# Jacdac_Pressure_Sensor-RevA-Maker.net
KiCad netlist of a schematic drawn in EAGLE
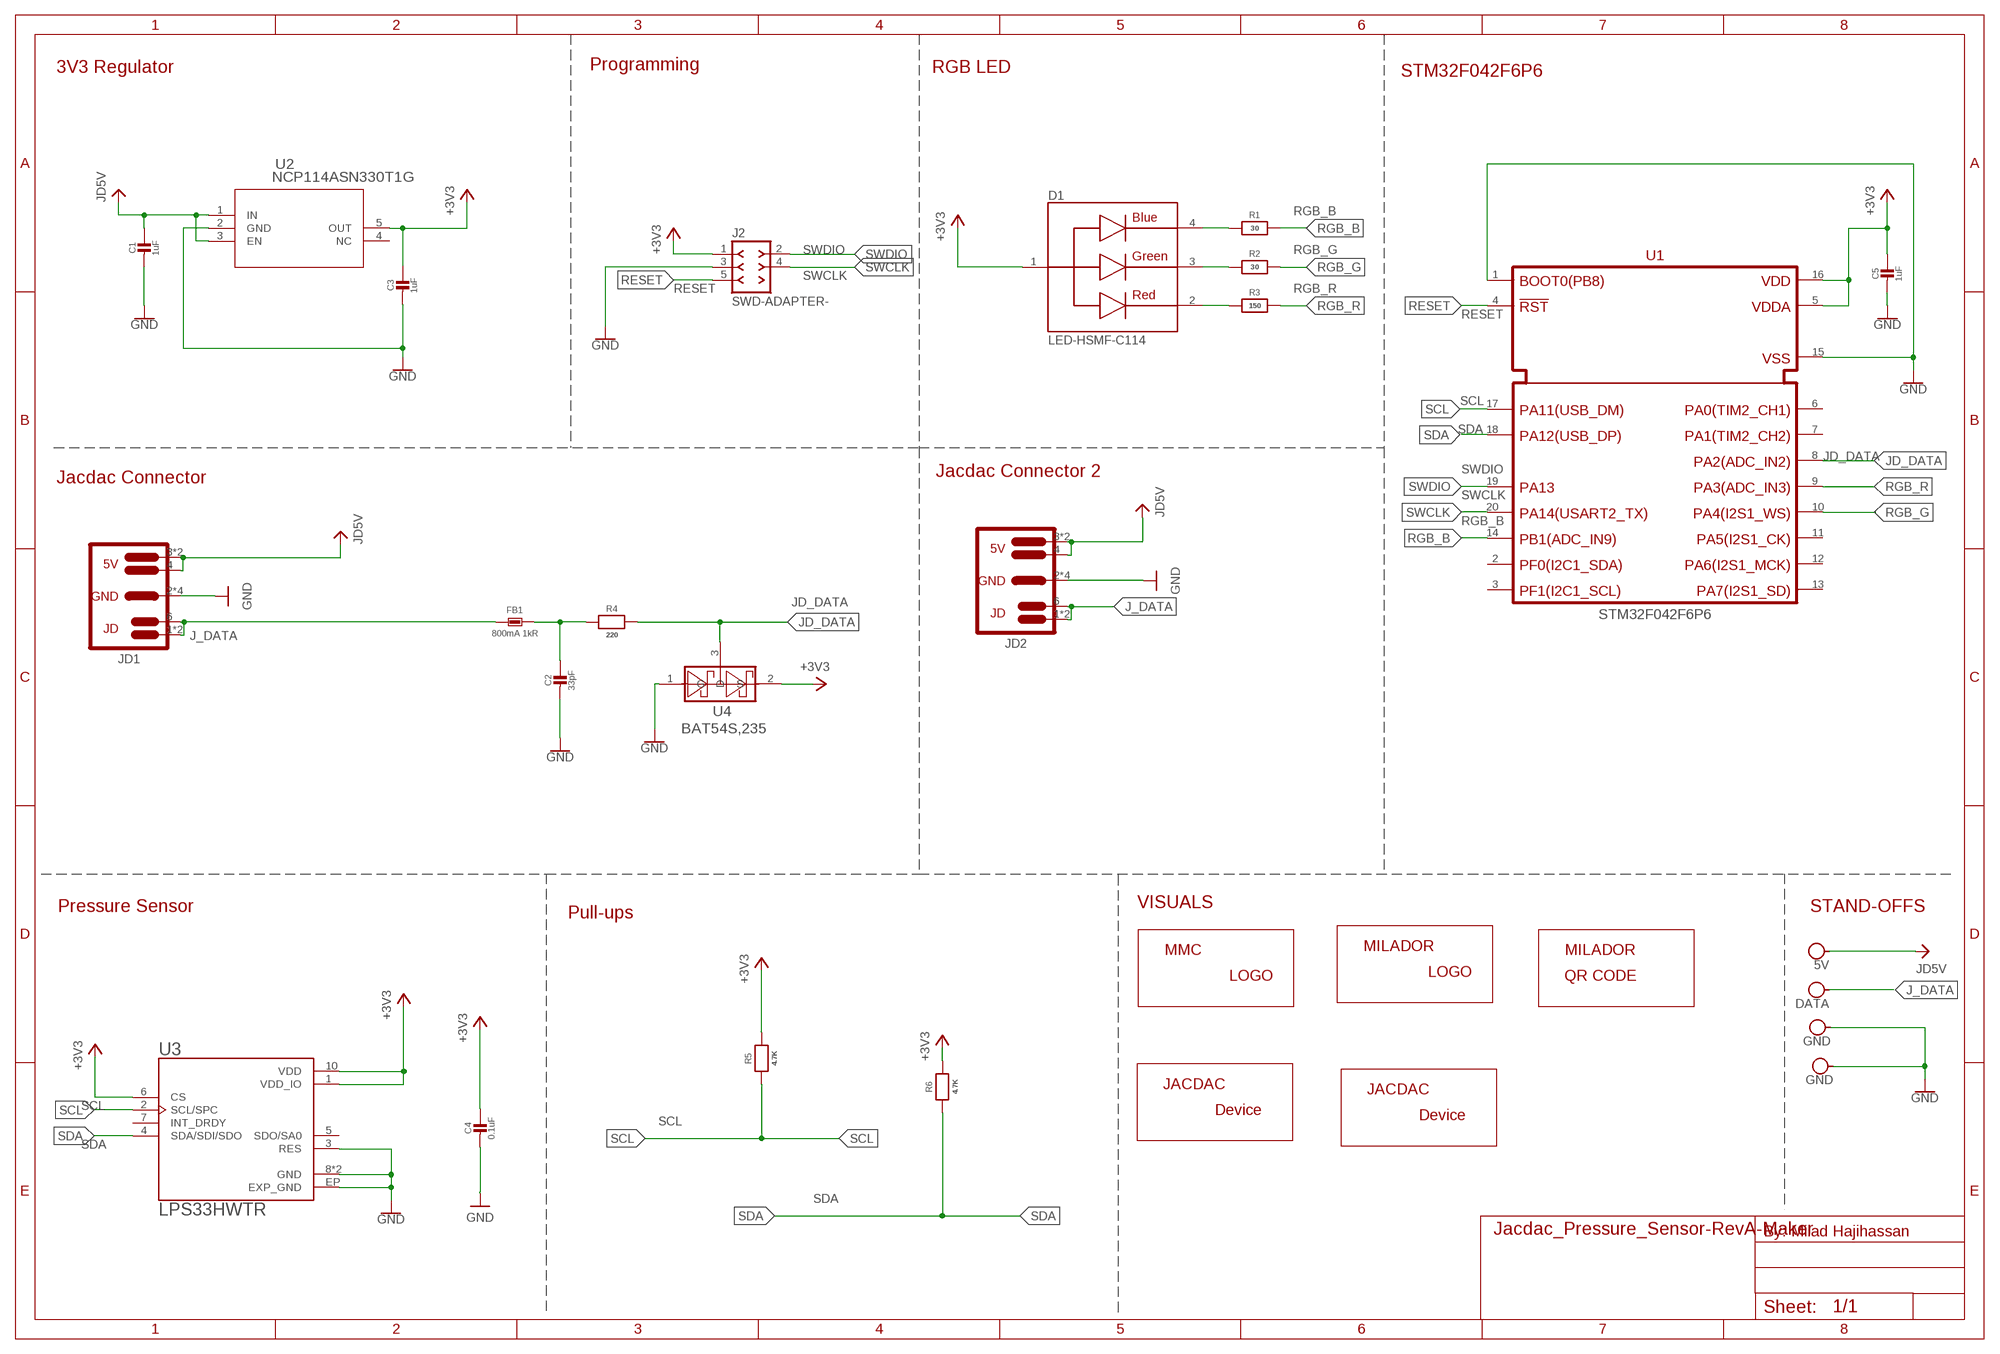
[diagram p0: schematic, sheet 1]

(export (version "E")
  (design (tool "Eeschema 10.0.6"))
  (components
    (comp (ref "C1")
      (value "1uF")
      (footprint "eagle-import:0603-NO")
      (libsource (lib "eagle-import") (part "CAP_CERAMIC-0603-NO"))
    )
    (comp (ref "C2")
      (value "33pF")
      (footprint "eagle-import:0603")
      (libsource (lib "eagle-import") (part "CAP_CERAMIC-0603"))
    )
    (comp (ref "C3")
      (value "1uF")
      (footprint "eagle-import:0603-NO")
      (libsource (lib "eagle-import") (part "CAP_CERAMIC-0603-NO"))
    )
    (comp (ref "C4")
      (value "0.1uF")
      (footprint "eagle-import:0603-NO")
      (libsource (lib "eagle-import") (part "CAP_CERAMIC-0603-NO"))
    )
    (comp (ref "C5")
      (value "1uF")
      (footprint "eagle-import:0603")
      (libsource (lib "eagle-import") (part "CAP_CERAMIC-0603"))
    )
    (comp (ref "D1")
      (value "LED-HSMF-C114")
      (footprint "eagle-import:DIOSC160X150X35-4N")
      (fields (field (name "MF") "Broadcom Limited") (field (name "MP") "HSMF-C114"))
      (libsource (lib "eagle-import") (part "LED-HSMF-C114"))
    )
    (comp (ref "FB1")
      (value "800mA 1kR")
      (footprint "eagle-import:0603-NO")
      (libsource (lib "eagle-import") (part "FERRITE-BEAD-0603-NO"))
    )
    (comp (ref "J2")
      (value "SWD-ADAPTER-")
      (footprint "eagle-import:SWD-ADAPTER")
      (libsource (lib "eagle-import") (part "SWD-ADAPTER-"))
    )
    (comp (ref "J3")
      (value "5V")
      (footprint "eagle-import:M3-HOLE-PWR-OUTL")
      (libsource (lib "eagle-import") (part "JACDAC-M3-PWR-OUTL"))
    )
    (comp (ref "J4")
      (value "DATA")
      (footprint "eagle-import:M3-HOLE-DATA-NOTCH")
      (libsource (lib "eagle-import") (part "JACDAC-M3-DATA-NOTCH"))
    )
    (comp (ref "J5")
      (value "GND")
      (footprint "eagle-import:M3-HOLE-GND")
      (libsource (lib "eagle-import") (part "JACDAC-M3-GND"))
    )
    (comp (ref "J6")
      (value "GND")
      (footprint "eagle-import:M3-HOLE-GND")
      (libsource (lib "eagle-import") (part "JACDAC-M3-GND"))
    )
    (comp (ref "JD1")
      (value "JACDAC-EDGE-OUTIE")
      (footprint "eagle-import:JD-EDGE-OUTIE")
      (libsource (lib "eagle-import") (part "JACDAC-EDGE-OUTIE"))
    )
    (comp (ref "JD2")
      (value "JACDAC-EDGE-OUTIE")
      (footprint "eagle-import:JD-EDGE-OUTIE")
      (libsource (lib "eagle-import") (part "JACDAC-EDGE-OUTIE"))
    )
    (comp (ref "LABEL_JACDAC_PS")
      (value "MILADOR-JACDAC-DEVICE-PS")
      (footprint "eagle-import:JACDAC-PRESSURE-SENSOR")
      (libsource (lib "eagle-import") (part "MILADOR-JACDAC-DEVICE-PS"))
    )
    (comp (ref "LABEL_LPS33HW")
      (value "MILADOR-JACDAC-DEVICE-LPS33HW")
      (footprint "eagle-import:JACDAC-LPS33HW")
      (libsource (lib "eagle-import") (part "MILADOR-JACDAC-DEVICE-LPS33HW"))
    )
    (comp (ref "LABEL_MILADOR")
      (value "MILADOR-LOGO-")
      (footprint "eagle-import:MILADOR_LOGO1")
      (libsource (lib "eagle-import") (part "MILADOR-LOGO-"))
    )
    (comp (ref "LABEL_QR_CODE")
      (value "MILADOR-QR-CODE-JACDAC-GITHUB-PS")
      (footprint "eagle-import:MILADOR_QR_JACDAC_PS")
      (libsource (lib "eagle-import") (part "MILADOR-QR-CODE-JACDAC-GITHUB-PS"))
    )
    (comp (ref "MMC_LOGO")
      (value "MMC_LOGO-XSM")
      (footprint "eagle-import:MMC_X-SMALL_LOGO")
      (libsource (lib "eagle-import") (part "MMC_LOGO-XSM"))
    )
    (comp (ref "R1")
      (value "30")
      (footprint "eagle-import:0603")
      (libsource (lib "eagle-import") (part "RESISTOR-0603"))
    )
    (comp (ref "R2")
      (value "30")
      (footprint "eagle-import:0603")
      (libsource (lib "eagle-import") (part "RESISTOR-0603"))
    )
    (comp (ref "R3")
      (value "150")
      (footprint "eagle-import:0603")
      (libsource (lib "eagle-import") (part "RESISTOR-0603"))
    )
    (comp (ref "R4")
      (value "220")
      (footprint "eagle-import:0603")
      (libsource (lib "eagle-import") (part "RESISTOR-0603"))
    )
    (comp (ref "R5")
      (value "4.7K")
      (footprint "eagle-import:0603")
      (libsource (lib "eagle-import") (part "RESISTOR-0603"))
    )
    (comp (ref "R6")
      (value "4.7K")
      (footprint "eagle-import:0603")
      (libsource (lib "eagle-import") (part "RESISTOR-0603"))
    )
    (comp (ref "U1")
      (value "STM32F042F6P6")
      (footprint "eagle-import:TSSOP20")
      (libsource (lib "eagle-import") (part "STM32F042F6P6"))
    )
    (comp (ref "U2")
      (value "NCP114ASN330T1G")
      (footprint "eagle-import:TSOP-5_ONS")
      (fields (field (name "COPYRIGHT") "Copyright (C) 2021 Ultra Librarian. All rights reserved."))
      (libsource (lib "eagle-import") (part "NCP114ASN330T1G"))
    )
    (comp (ref "U3")
      (value "LPS33HWTR")
      (footprint "eagle-import:PQFN60P330X330X290-11N")
      (fields (field (name "DIGI-KEY_PART_NUMBER") "497-17590-1-ND") (field (name "MF") "STMicroelectronics"))
      (libsource (lib "eagle-import") (part "LPS33HWTR"))
    )
    (comp (ref "U4")
      (value "BAT54S,235")
      (footprint "eagle-import:SOT23-3")
      (fields (field (name "MF") "Diodes") (field (name "MP") "BSS138-7-F"))
      (libsource (lib "eagle-import") (part "BAT54S,235"))
    )
  )
  (nets
    (net (code "1") (name "+3V3") (class "Default")
      (node (ref "C3") (pin "1") (pinfunction "1_1") (pintype "passive"))
      (node (ref "C4") (pin "1") (pinfunction "1_1") (pintype "passive"))
      (node (ref "C5") (pin "1") (pinfunction "1_1") (pintype "passive"))
      (node (ref "D1") (pin "1") (pinfunction "1_1") (pintype "passive"))
      (node (ref "J2") (pin "1") (pinfunction "VCC_1_1") (pintype "passive"))
      (node (ref "R5") (pin "2") (pinfunction "2_2") (pintype "passive"))
      (node (ref "R6") (pin "2") (pinfunction "2_2") (pintype "passive"))
      (node (ref "U1") (pin "16") (pinfunction "VDD_16") (pintype "input"))
      (node (ref "U1") (pin "5") (pinfunction "VDDA_5") (pintype "input"))
      (node (ref "U2") (pin "5") (pinfunction "OUT_5") (pintype "power_in"))
      (node (ref "U3") (pin "1") (pinfunction "VDD_IO_1") (pintype "power_in"))
      (node (ref "U3") (pin "10") (pinfunction "VDD_10") (pintype "power_in"))
      (node (ref "U3") (pin "6") (pinfunction "CS_6") (pintype "bidirectional"))
      (node (ref "U4") (pin "2") (pinfunction "S_2") (pintype "passive"))
    )
    (net (code "2") (name "GND") (class "Default")
      (node (ref "C1") (pin "2") (pinfunction "2_2") (pintype "passive"))
      (node (ref "C2") (pin "2") (pinfunction "2_2") (pintype "passive"))
      (node (ref "C3") (pin "2") (pinfunction "2_2") (pintype "passive"))
      (node (ref "C4") (pin "2") (pinfunction "2_2") (pintype "passive"))
      (node (ref "C5") (pin "2") (pinfunction "2_2") (pintype "passive"))
      (node (ref "J2") (pin "3") (pinfunction "GND_3_3") (pintype "passive"))
      (node (ref "J5") (pin "H") (pinfunction "P$1_H") (pintype "bidirectional"))
      (node (ref "J6") (pin "H") (pinfunction "P$1_H") (pintype "bidirectional"))
      (node (ref "JD1") (pin "2") (pinfunction "1_2") (pintype "power_in"))
      (node (ref "JD1") (pin "5") (pinfunction "1_5") (pintype "power_in"))
      (node (ref "JD1") (pin "P$2") (pinfunction "1_P$2") (pintype "power_in"))
      (node (ref "JD1") (pin "P$4") (pinfunction "1_P$4") (pintype "power_in"))
      (node (ref "JD2") (pin "2") (pinfunction "1_2") (pintype "power_in"))
      (node (ref "JD2") (pin "5") (pinfunction "1_5") (pintype "power_in"))
      (node (ref "JD2") (pin "P$2") (pinfunction "1_P$2") (pintype "power_in"))
      (node (ref "JD2") (pin "P$4") (pinfunction "1_P$4") (pintype "power_in"))
      (node (ref "U1") (pin "1") (pinfunction "BOOT0_1") (pintype "input"))
      (node (ref "U1") (pin "15") (pinfunction "VSS_15") (pintype "input"))
      (node (ref "U2") (pin "2") (pinfunction "GND_2") (pintype "passive"))
      (node (ref "U3") (pin "3") (pinfunction "RES_3") (pintype "passive"))
      (node (ref "U3") (pin "8") (pinfunction "GND_8") (pintype "power_in"))
      (node (ref "U3") (pin "9") (pinfunction "GND_9") (pintype "power_in"))
      (node (ref "U3") (pin "EP") (pinfunction "EXP_GND_EP") (pintype "power_in"))
      (node (ref "U4") (pin "1") (pinfunction "G_1") (pintype "passive"))
    )
    (net (code "3") (name "JD5V") (class "Default")
      (node (ref "C1") (pin "1") (pinfunction "1_1") (pintype "passive"))
      (node (ref "J3") (pin "H") (pinfunction "P$1_H") (pintype "bidirectional"))
      (node (ref "JD1") (pin "3") (pinfunction "3_3") (pintype "power_in"))
      (node (ref "JD1") (pin "4") (pinfunction "4_4") (pintype "power_in"))
      (node (ref "JD1") (pin "P$1") (pinfunction "3_P$1") (pintype "power_in"))
      (node (ref "JD2") (pin "3") (pinfunction "3_3") (pintype "power_in"))
      (node (ref "JD2") (pin "4") (pinfunction "4_4") (pintype "power_in"))
      (node (ref "JD2") (pin "P$1") (pinfunction "3_P$1") (pintype "power_in"))
      (node (ref "U2") (pin "1") (pinfunction "IN_1") (pintype "input"))
      (node (ref "U2") (pin "3") (pinfunction "EN_3") (pintype "passive"))
    )
    (net (code "4") (name "JD_DATA") (class "Default")
      (node (ref "R4") (pin "2") (pinfunction "2_2") (pintype "passive"))
      (node (ref "U1") (pin "8") (pinfunction "PA2_8") (pintype "bidirectional"))
      (node (ref "U4") (pin "3") (pinfunction "D_3") (pintype "passive"))
    )
    (net (code "5") (name "J_DATA") (class "Default")
      (node (ref "FB1") (pin "2") (pinfunction "2_2") (pintype "passive"))
      (node (ref "J4") (pin "H") (pinfunction "P$1_H") (pintype "bidirectional"))
      (node (ref "JD1") (pin "1") (pinfunction "2_1") (pintype "bidirectional"))
      (node (ref "JD1") (pin "6") (pinfunction "6_6") (pintype "bidirectional"))
      (node (ref "JD1") (pin "P$3") (pinfunction "2_P$3") (pintype "bidirectional"))
      (node (ref "JD2") (pin "1") (pinfunction "2_1") (pintype "bidirectional"))
      (node (ref "JD2") (pin "6") (pinfunction "6_6") (pintype "bidirectional"))
      (node (ref "JD2") (pin "P$3") (pinfunction "2_P$3") (pintype "bidirectional"))
    )
    (net (code "6") (name "Net-(C2-Pad1)") (class "Default")
      (node (ref "C2") (pin "1") (pinfunction "1_1") (pintype "passive"))
      (node (ref "FB1") (pin "1") (pinfunction "1_1") (pintype "passive"))
      (node (ref "R4") (pin "1") (pinfunction "1_1") (pintype "passive"))
    )
    (net (code "7") (name "Net-(D1-Pad2)") (class "Default")
      (node (ref "D1") (pin "2") (pinfunction "2_2") (pintype "passive"))
      (node (ref "R3") (pin "1") (pinfunction "1_1") (pintype "passive"))
    )
    (net (code "8") (name "Net-(D1-Pad3)") (class "Default")
      (node (ref "D1") (pin "3") (pinfunction "3_3") (pintype "passive"))
      (node (ref "R2") (pin "1") (pinfunction "1_1") (pintype "passive"))
    )
    (net (code "9") (name "Net-(D1-Pad4)") (class "Default")
      (node (ref "D1") (pin "4") (pinfunction "4_4") (pintype "passive"))
      (node (ref "R1") (pin "1") (pinfunction "1_1") (pintype "passive"))
    )
    (net (code "10") (name "RESET") (class "Default")
      (node (ref "J2") (pin "5") (pinfunction "RESET_5_5") (pintype "passive"))
      (node (ref "U1") (pin "4") (pinfunction "~{RST}_4") (pintype "input"))
    )
    (net (code "11") (name "RGB_B") (class "Default")
      (node (ref "R1") (pin "2") (pinfunction "2_2") (pintype "passive"))
      (node (ref "U1") (pin "14") (pinfunction "PB1_14") (pintype "bidirectional"))
    )
    (net (code "12") (name "RGB_G") (class "Default")
      (node (ref "R2") (pin "2") (pinfunction "2_2") (pintype "passive"))
      (node (ref "U1") (pin "10") (pinfunction "PA4_10") (pintype "bidirectional"))
    )
    (net (code "13") (name "RGB_R") (class "Default")
      (node (ref "R3") (pin "2") (pinfunction "2_2") (pintype "passive"))
      (node (ref "U1") (pin "9") (pinfunction "PA3_9") (pintype "bidirectional"))
    )
    (net (code "14") (name "SCL") (class "Default")
      (node (ref "R5") (pin "1") (pinfunction "1_1") (pintype "passive"))
      (node (ref "U1") (pin "17") (pinfunction "PA11_17") (pintype "bidirectional"))
      (node (ref "U3") (pin "2") (pinfunction "SCL/SPC_2") (pintype "input"))
    )
    (net (code "15") (name "SDA") (class "Default")
      (node (ref "R6") (pin "1") (pinfunction "1_1") (pintype "passive"))
      (node (ref "U1") (pin "18") (pinfunction "PA12_18") (pintype "bidirectional"))
      (node (ref "U3") (pin "4") (pinfunction "SDA/SDI/SDO_4") (pintype "bidirectional"))
    )
    (net (code "16") (name "SWCLK") (class "Default")
      (node (ref "J2") (pin "4") (pinfunction "SWCLK_4_4") (pintype "passive"))
      (node (ref "U1") (pin "20") (pinfunction "PA14_20") (pintype "bidirectional"))
    )
    (net (code "17") (name "SWDIO") (class "Default")
      (node (ref "J2") (pin "2") (pinfunction "SWDIO_2_2") (pintype "passive"))
      (node (ref "U1") (pin "19") (pinfunction "PA13_19") (pintype "bidirectional"))
    )
    (net (code "18") (name "unconnected-(U1-PA0-Pad6)") (class "Default")
      (node (ref "U1") (pin "6") (pinfunction "PA0_6") (pintype "bidirectional"))
    )
    (net (code "19") (name "unconnected-(U1-PA1-Pad7)") (class "Default")
      (node (ref "U1") (pin "7") (pinfunction "PA1_7") (pintype "bidirectional"))
    )
    (net (code "20") (name "unconnected-(U1-PA5-Pad11)") (class "Default")
      (node (ref "U1") (pin "11") (pinfunction "PA5_11") (pintype "bidirectional"))
    )
    (net (code "21") (name "unconnected-(U1-PA6-Pad12)") (class "Default")
      (node (ref "U1") (pin "12") (pinfunction "PA6_12") (pintype "bidirectional"))
    )
    (net (code "22") (name "unconnected-(U1-PA7-Pad13)") (class "Default")
      (node (ref "U1") (pin "13") (pinfunction "PA7_13") (pintype "bidirectional"))
    )
    (net (code "23") (name "unconnected-(U1-PF0-Pad2)") (class "Default")
      (node (ref "U1") (pin "2") (pinfunction "PF0_2") (pintype "bidirectional"))
    )
    (net (code "24") (name "unconnected-(U1-PF1-Pad3)") (class "Default")
      (node (ref "U1") (pin "3") (pinfunction "PF1_3") (pintype "bidirectional"))
    )
    (net (code "25") (name "unconnected-(U2-NC-Pad4)") (class "Default")
      (node (ref "U2") (pin "4") (pinfunction "NC_4") (pintype "no_connect"))
    )
    (net (code "26") (name "unconnected-(U3-INT_DRDY-Pad7)") (class "Default")
      (node (ref "U3") (pin "7") (pinfunction "INT_DRDY_7") (pintype "bidirectional"))
    )
    (net (code "27") (name "unconnected-(U3-SDO{slash}SA0-Pad5)") (class "Default")
      (node (ref "U3") (pin "5") (pinfunction "SDO/SA0_5") (pintype "output"))
    )
  )
)
